# drvcomm.net
KiCad netlist of a schematic drawn in Altium Designer
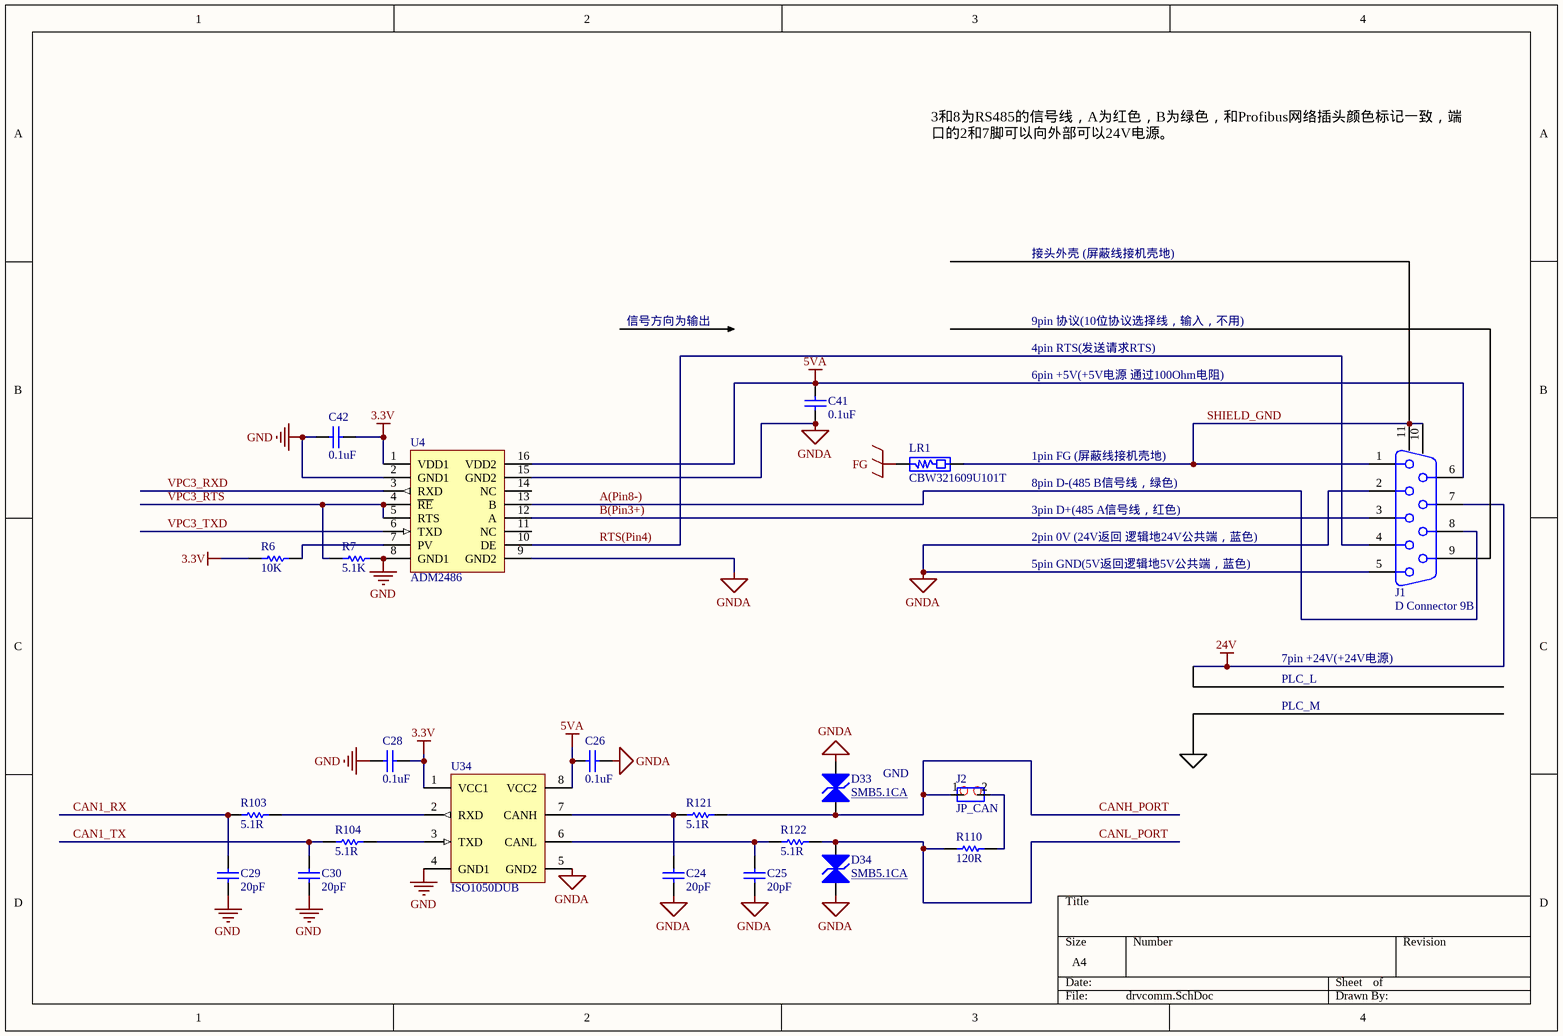
[diagram p0: drvcomm.SchDoc]

(export (version "E")
  (design (tool "Eeschema 10.0.6"))
  (components
    (comp (ref "C24")
      (value "20pF")
      (footprint "CAPC2012M")
      (description "Capacitor")
      (fields (field (name "PUBLISHER") "Altium Limited"))
      (libsource (lib "Miscellaneous Devices") (part "Cap"))
    )
    (comp (ref "C25")
      (value "20pF")
      (footprint "CAPC2012M")
      (description "Capacitor")
      (fields (field (name "PUBLISHER") "Altium Limited"))
      (libsource (lib "Miscellaneous Devices") (part "Cap"))
    )
    (comp (ref "C26")
      (value "0.1uF")
      (footprint "CAPC2012M")
      (description "Capacitor")
      (fields (field (name "PUBLISHER") "Altium Limited"))
      (libsource (lib "Miscellaneous Devices") (part "Cap"))
    )
    (comp (ref "C28")
      (value "0.1uF")
      (footprint "CAPC2012M")
      (description "Capacitor")
      (fields (field (name "PUBLISHER") "Altium Limited"))
      (libsource (lib "Miscellaneous Devices") (part "Cap"))
    )
    (comp (ref "C29")
      (value "20pF")
      (footprint "CAPC2012M")
      (description "Capacitor")
      (fields (field (name "PUBLISHER") "Altium Limited"))
      (libsource (lib "Miscellaneous Devices") (part "Cap"))
    )
    (comp (ref "C30")
      (value "20pF")
      (footprint "CAPC2012M")
      (description "Capacitor")
      (fields (field (name "PUBLISHER") "Altium Limited"))
      (libsource (lib "Miscellaneous Devices") (part "Cap"))
    )
    (comp (ref "C41")
      (value "0.1uF")
      (footprint "CAPC2012M")
      (description "Capacitor")
      (fields (field (name "PUBLISHER") "Altium Limited"))
      (libsource (lib "Miscellaneous Devices") (part "Cap"))
    )
    (comp (ref "C42")
      (value "0.1uF")
      (footprint "CAPC2012M")
      (description "Capacitor")
      (fields (field (name "PUBLISHER") "Altium Limited"))
      (libsource (lib "Miscellaneous Devices") (part "Cap"))
    )
    (comp (ref "D33")
      (value "SMB5.1CA")
      (footprint "SMB")
      (description "Bi-dir TVS Diode")
      (fields (field (name "PUBLISHER") "Altium Limited"))
      (libsource (lib "UserLib") (part "Bi-dir TVS Diode"))
    )
    (comp (ref "D34")
      (value "SMB5.1CA")
      (footprint "SMB")
      (description "Bi-dir TVS Diode")
      (fields (field (name "PUBLISHER") "Altium Limited"))
      (libsource (lib "UserLib") (part "Bi-dir TVS Diode"))
    )
    (comp (ref "J1")
      (value "D Connector 9B")
      (footprint "DSUB1.385-2H9BL")
      (description "Receptacle Assembly, 9 Position, Upright")
      (fields (field (name "PUBLISHER") "Altium Limited"))
      (libsource (lib "UserSchCon") (part "D Connector 9B"))
    )
    (comp (ref "J2")
      (value "JP_CAN")
      (footprint "DS-01")
      (description "'Dial Switch pitch 7.62mm")
      (libsource (lib "UserLib") (part "JK2H"))
    )
    (comp (ref "LR1")
      (value "CBW321609U101T")
      (footprint "INDC3216M")
      (description "EMI FILTERS,DC Resistance max.0.05~1.5 ohms,10 ~ 1000 ohms at 100MHz  Frequency")
      (libsource (lib "UserLib") (part "BLM10/11/21/31/41"))
    )
    (comp (ref "R6")
      (value "10K")
      (footprint "RESC2012M")
      (description "Resistor")
      (fields (field (name "PUBLISHER") "Altium Limited"))
      (libsource (lib "Miscellaneous Devices") (part "Res1"))
    )
    (comp (ref "R7")
      (value "5.1K")
      (footprint "RESC2012M")
      (description "Resistor")
      (fields (field (name "PUBLISHER") "Altium Limited"))
      (libsource (lib "Miscellaneous Devices") (part "Res1"))
    )
    (comp (ref "R103")
      (value "5.1R")
      (footprint "RESC2012M")
      (description "Resistor")
      (fields (field (name "PUBLISHER") "Altium Limited"))
      (libsource (lib "Miscellaneous Devices") (part "Res1"))
    )
    (comp (ref "R104")
      (value "5.1R")
      (footprint "RESC2012M")
      (description "Resistor")
      (fields (field (name "PUBLISHER") "Altium Limited"))
      (libsource (lib "Miscellaneous Devices") (part "Res1"))
    )
    (comp (ref "R110")
      (value "120R")
      (footprint "RESC2012M")
      (description "Resistor")
      (fields (field (name "PUBLISHER") "Altium Limited"))
      (libsource (lib "Miscellaneous Devices") (part "Res1"))
    )
    (comp (ref "R121")
      (value "5.1R")
      (footprint "RESC2012M")
      (description "Resistor")
      (fields (field (name "PUBLISHER") "Altium Limited"))
      (libsource (lib "Miscellaneous Devices") (part "Res1"))
    )
    (comp (ref "R122")
      (value "5.1R")
      (footprint "RESC2012M")
      (description "Resistor")
      (fields (field (name "PUBLISHER") "Altium Limited"))
      (libsource (lib "Miscellaneous Devices") (part "Res1"))
    )
    (comp (ref "U4")
      (value "ADM2486")
      (footprint "RW-16_N")
      (description "Isolated RS-485 Transceiver")
      (libsource (lib "UserSchDev") (part "ADM2486"))
    )
    (comp (ref "U34")
      (value "ISO1050DUB")
      (footprint "SO-8LA")
      (description "隔离型CAN接口芯片")
      (libsource (lib "UserSchDev") (part "ISO1050DUB"))
    )
  )
  (nets
    (net (code "1") (name "/A(Pin8-)") (class "Default")
      (node (ref "J1") (pin "8") (pinfunction "8_8") (pintype "passive"))
      (node (ref "U4") (pin "13") (pinfunction "B_13") (pintype "passive"))
    )
    (net (code "2") (name "/B(Pin3+)") (class "Default")
      (node (ref "J1") (pin "3") (pinfunction "3_3") (pintype "passive"))
      (node (ref "U4") (pin "12") (pinfunction "A_12") (pintype "passive"))
    )
    (net (code "3") (name "/CAN1_RX") (class "Default")
      (node (ref "C29") (pin "2") (pinfunction "2_2") (pintype "passive"))
      (node (ref "R103") (pin "2") (pinfunction "2_2") (pintype "passive"))
    )
    (net (code "4") (name "/CAN1_TX") (class "Default")
      (node (ref "C30") (pin "2") (pinfunction "2_2") (pintype "passive"))
      (node (ref "R104") (pin "2") (pinfunction "2_2") (pintype "passive"))
    )
    (net (code "5") (name "/CANH_PORT") (class "Default")
      (node (ref "D33") (pin "2") (pinfunction "K_2") (pintype "passive"))
      (node (ref "J2") (pin "1") (pintype "passive"))
      (node (ref "R121") (pin "1") (pinfunction "1_1") (pintype "passive"))
    )
    (net (code "6") (name "/CANL_PORT") (class "Default")
      (node (ref "D34") (pin "2") (pinfunction "K_2") (pintype "passive"))
      (node (ref "R110") (pin "2") (pinfunction "2_2") (pintype "passive"))
      (node (ref "R122") (pin "1") (pinfunction "1_1") (pintype "passive"))
    )
    (net (code "7") (name "/RTS(Pin4)") (class "Default")
      (node (ref "J1") (pin "4") (pinfunction "4_4") (pintype "passive"))
      (node (ref "U4") (pin "10") (pinfunction "DE_10") (pintype "passive"))
    )
    (net (code "8") (name "/SHIELD_GND") (class "Default")
      (node (ref "J1") (pin "1") (pinfunction "1_1") (pintype "passive"))
      (node (ref "J1") (pin "10") (pinfunction "MH1_10") (pintype "passive"))
      (node (ref "J1") (pin "11") (pinfunction "MH2_11") (pintype "passive"))
      (node (ref "LR1") (pin "2") (pinfunction "2_2") (pintype "passive"))
    )
    (net (code "9") (name "/VPC3_RTS") (class "Default")
      (node (ref "R7") (pin "2") (pinfunction "2_2") (pintype "passive"))
      (node (ref "U4") (pin "4") (pinfunction "~{RE}_4") (pintype "passive"))
      (node (ref "U4") (pin "5") (pinfunction "RTS_5") (pintype "passive"))
    )
    (net (code "10") (name "/VPC3_RXD") (class "Default")
      (node (ref "U4") (pin "3") (pinfunction "RXD_3") (pintype "output"))
    )
    (net (code "11") (name "/VPC3_TXD") (class "Default")
      (node (ref "U4") (pin "6") (pinfunction "TXD_6") (pintype "input"))
    )
    (net (code "12") (name "3.3V") (class "Default")
      (node (ref "C28") (pin "1") (pinfunction "1_1") (pintype "passive"))
      (node (ref "C42") (pin "1") (pinfunction "1_1") (pintype "passive"))
      (node (ref "R6") (pin "1") (pinfunction "1_1") (pintype "passive"))
      (node (ref "U34") (pin "1") (pinfunction "VCC1_1") (pintype "power_in"))
      (node (ref "U4") (pin "1") (pinfunction "VDD1_1") (pintype "power_in"))
    )
    (net (code "13") (name "5VA") (class "Default")
      (node (ref "C26") (pin "1") (pinfunction "1_1") (pintype "passive"))
      (node (ref "C41") (pin "1") (pinfunction "1_1") (pintype "passive"))
      (node (ref "J1") (pin "6") (pinfunction "6_6") (pintype "passive"))
      (node (ref "U34") (pin "8") (pinfunction "VCC2_8") (pintype "power_in"))
      (node (ref "U4") (pin "16") (pinfunction "VDD2_16") (pintype "power_in"))
    )
    (net (code "14") (name "24V") (class "Default")
      (node (ref "J1") (pin "7") (pinfunction "7_7") (pintype "passive"))
    )
    (net (code "15") (name "FG") (class "Default")
      (node (ref "LR1") (pin "1") (pinfunction "1_1") (pintype "passive"))
    )
    (net (code "16") (name "GND") (class "Default")
      (node (ref "C28") (pin "2") (pinfunction "2_2") (pintype "passive"))
      (node (ref "C29") (pin "1") (pinfunction "1_1") (pintype "passive"))
      (node (ref "C30") (pin "1") (pinfunction "1_1") (pintype "passive"))
      (node (ref "C42") (pin "2") (pinfunction "2_2") (pintype "passive"))
      (node (ref "R7") (pin "1") (pinfunction "1_1") (pintype "passive"))
      (node (ref "U34") (pin "4") (pinfunction "GND1_4") (pintype "power_in"))
      (node (ref "U4") (pin "2") (pinfunction "GND1_2") (pintype "power_in"))
      (node (ref "U4") (pin "8") (pinfunction "GND1_8") (pintype "power_in"))
    )
    (net (code "17") (name "GNDA") (class "Default")
      (node (ref "C24") (pin "1") (pinfunction "1_1") (pintype "passive"))
      (node (ref "C25") (pin "1") (pinfunction "1_1") (pintype "passive"))
      (node (ref "C26") (pin "2") (pinfunction "2_2") (pintype "passive"))
      (node (ref "C41") (pin "2") (pinfunction "2_2") (pintype "passive"))
      (node (ref "D33") (pin "1") (pinfunction "A_1") (pintype "passive"))
      (node (ref "D34") (pin "1") (pinfunction "A_1") (pintype "passive"))
      (node (ref "J1") (pin "2") (pinfunction "2_2") (pintype "passive"))
      (node (ref "J1") (pin "5") (pinfunction "5_5") (pintype "passive"))
      (node (ref "U34") (pin "5") (pinfunction "GND2_5") (pintype "power_in"))
      (node (ref "U4") (pin "15") (pinfunction "GND2_15") (pintype "passive"))
      (node (ref "U4") (pin "9") (pinfunction "GND2_9") (pintype "power_in"))
    )
    (net (code "18") (name "Net-(J2-Pad2)") (class "Default")
      (node (ref "J2") (pin "2") (pintype "passive"))
      (node (ref "R110") (pin "1") (pinfunction "1_1") (pintype "passive"))
    )
    (net (code "19") (name "Net-(U4-PV)") (class "Default")
      (node (ref "R6") (pin "2") (pinfunction "2_2") (pintype "passive"))
      (node (ref "U4") (pin "7") (pinfunction "PV_7") (pintype "passive"))
    )
    (net (code "20") (name "Net-(U34-CANH)") (class "Default")
      (node (ref "C24") (pin "2") (pinfunction "2_2") (pintype "passive"))
      (node (ref "R121") (pin "2") (pinfunction "2_2") (pintype "passive"))
      (node (ref "U34") (pin "7") (pinfunction "CANH_7") (pintype "passive"))
    )
    (net (code "21") (name "Net-(U34-CANL)") (class "Default")
      (node (ref "C25") (pin "2") (pinfunction "2_2") (pintype "passive"))
      (node (ref "R122") (pin "2") (pinfunction "2_2") (pintype "passive"))
      (node (ref "U34") (pin "6") (pinfunction "CANL_6") (pintype "passive"))
    )
    (net (code "22") (name "Net-(U34-RXD)") (class "Default")
      (node (ref "R103") (pin "1") (pinfunction "1_1") (pintype "passive"))
      (node (ref "U34") (pin "2") (pinfunction "RXD_2") (pintype "output"))
    )
    (net (code "23") (name "Net-(U34-TXD)") (class "Default")
      (node (ref "R104") (pin "1") (pinfunction "1_1") (pintype "passive"))
      (node (ref "U34") (pin "3") (pinfunction "TXD_3") (pintype "input"))
    )
    (net (code "24") (name "unconnected-(J1-Pad9)") (class "Default")
      (node (ref "J1") (pin "9") (pinfunction "9_9") (pintype "passive"))
    )
    (net (code "25") (name "unconnected-(U4-NC-Pad11)") (class "Default")
      (node (ref "U4") (pin "11") (pinfunction "NC_11") (pintype "passive"))
    )
    (net (code "26") (name "unconnected-(U4-NC-Pad14)") (class "Default")
      (node (ref "U4") (pin "14") (pinfunction "NC_14") (pintype "passive"))
    )
  )
)
